# Laadstation.net
KiCad netlist of a schematic drawn in Altium Designer
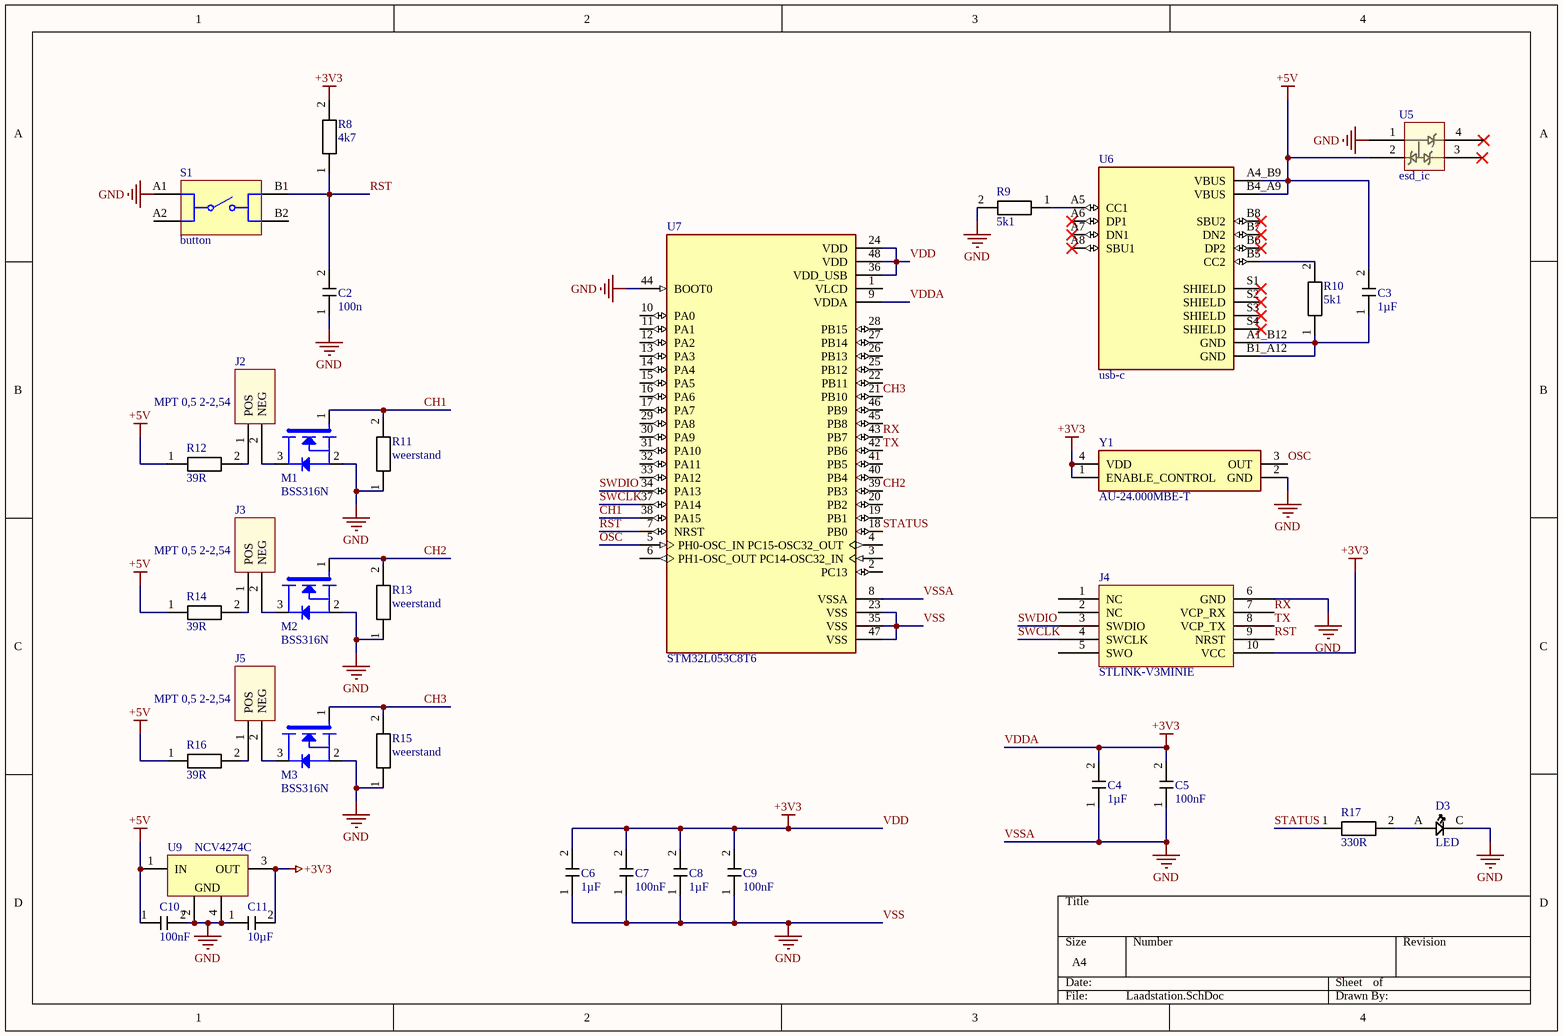
[diagram p0: Laadstation.SchDoc]

(export (version "E")
  (design (tool "Eeschema 10.0.6"))
  (components
    (comp (ref "C2") (value "100n") (footprint "0603") (libsource (lib "condensator") (part "Condensator")))
    (comp (ref "C3") (value "1µF") (footprint "0603") (libsource (lib "condensator") (part "Condensator")))
    (comp (ref "C4") (value "1µF") (footprint "0603") (libsource (lib "Schlib1") (part "cap")))
    (comp (ref "C5") (value "100nF") (footprint "0603") (libsource (lib "Schlib1") (part "cap")))
    (comp (ref "C6") (value "1µF") (footprint "0603") (libsource (lib "condensator") (part "Condensator")))
    (comp (ref "C7") (value "100nF") (footprint "0603") (libsource (lib "condensator") (part "Condensator")))
    (comp (ref "C8") (value "1µF") (footprint "0603") (libsource (lib "condensator") (part "Condensator")))
    (comp (ref "C9") (value "100nF") (footprint "0603") (libsource (lib "condensator") (part "Condensator")))
    (comp (ref "C10") (value "100nF") (footprint "0603") (libsource (lib "Schlib1") (part "cap")))
    (comp (ref "C11") (value "10µF") (footprint "0603") (libsource (lib "Schlib1") (part "cap")))
    (comp (ref "D3") (value "LED") (footprint "LED") (libsource (lib "Schlib1") (part "LED")))
    (comp (ref "J2")
      (value "MPT 0,5 2-2,54")
      (footprint "MPT 0,5 2-2,54")
      (libsource (lib "Schlib1") (part "MPT 0,5 2-2,54"))
    )
    (comp (ref "J3")
      (value "MPT 0,5 2-2,54")
      (footprint "MPT 0,5 2-2,54")
      (libsource (lib "Schlib1") (part "MPT 0,5 2-2,54"))
    )
    (comp (ref "J4")
      (value "STLINK-V3MINIE")
      (footprint "STLINK-V3MINIE")
      (libsource (lib "Schlib1") (part "STLINK-V3MINIE"))
    )
    (comp (ref "J5")
      (value "MPT 0,5 2-2,54")
      (footprint "MPT 0,5 2-2,54")
      (libsource (lib "Schlib1") (part "MPT 0,5 2-2,54"))
    )
    (comp (ref "M1") (value "BSS316N") (footprint "BSS316N") (libsource (lib "Schlib1") (part "BSS316N")))
    (comp (ref "M2") (value "BSS316N") (footprint "BSS316N") (libsource (lib "Schlib1") (part "BSS316N")))
    (comp (ref "M3") (value "BSS316N") (footprint "BSS316N") (libsource (lib "Schlib1") (part "BSS316N")))
    (comp (ref "R8") (value "4k7") (footprint "0603") (libsource (lib "Schlib1") (part "weerstand")))
    (comp (ref "R9") (value "5k1") (footprint "0603") (libsource (lib "Schlib1") (part "weerstand")))
    (comp (ref "R10") (value "5k1") (footprint "0603") (libsource (lib "Schlib1") (part "weerstand")))
    (comp (ref "R11") (value "weerstand") (footprint "0603") (libsource (lib "Schlib1") (part "weerstand")))
    (comp (ref "R12") (value "39R") (footprint "0603") (libsource (lib "Schlib1") (part "weerstand")))
    (comp (ref "R13") (value "weerstand") (footprint "0603") (libsource (lib "Schlib1") (part "weerstand")))
    (comp (ref "R14") (value "39R") (footprint "0603") (libsource (lib "Schlib1") (part "weerstand")))
    (comp (ref "R15") (value "weerstand") (footprint "0603") (libsource (lib "Schlib1") (part "weerstand")))
    (comp (ref "R16") (value "39R") (footprint "0603") (libsource (lib "Schlib1") (part "weerstand")))
    (comp (ref "R17") (value "330R") (footprint "0603") (libsource (lib "Schlib1") (part "weerstand")))
    (comp (ref "S1") (value "button") (footprint "BUTTON") (libsource (lib "Schlib1") (part "button")))
    (comp (ref "U5") (value "esd_ic") (footprint "esd_ic") (libsource (lib "Schlib1") (part "esd_ic")))
    (comp (ref "U6") (value "usb-c") (footprint "usb-c") (libsource (lib "Schlib1") (part "usb-c")))
    (comp (ref "U7")
      (value "STM32L053C8T6")
      (footprint "stm32l053c8t6")
      (libsource (lib "Schlib1") (part "STM32L053C8T6"))
    )
    (comp (ref "U9") (value "NCV4274C") (footprint "NCV4274C") (libsource (lib "Schlib1") (part "NCV4274C")))
    (comp (ref "Y1")
      (value "AU-24.000MBE-T")
      (footprint "AU-24.000MBE-T")
      (libsource (lib "Schlib1") (part "AU-24.000MBE-T"))
    )
  )
  (nets
    (net (code "1") (name "+3V3") (class "Default")
      (node (ref "C11") (pin "2") (pinfunction "G_2") (pintype "passive"))
      (node (ref "C4") (pin "2") (pinfunction "G_2") (pintype "passive"))
      (node (ref "C5") (pin "2") (pinfunction "G_2") (pintype "passive"))
      (node (ref "C6") (pin "2") (pinfunction "G_2") (pintype "passive"))
      (node (ref "C7") (pin "2") (pinfunction "G_2") (pintype "passive"))
      (node (ref "C8") (pin "2") (pinfunction "G_2") (pintype "passive"))
      (node (ref "C9") (pin "2") (pinfunction "G_2") (pintype "passive"))
      (node (ref "J4") (pin "10") (pinfunction "VCC_10") (pintype "passive"))
      (node (ref "R8") (pin "2") (pinfunction "G_2") (pintype "passive"))
      (node (ref "U7") (pin "24") (pinfunction "VDD_24") (pintype "power_in"))
      (node (ref "U7") (pin "36") (pinfunction "VDD_USB_36") (pintype "power_in"))
      (node (ref "U7") (pin "48") (pinfunction "VDD_48") (pintype "power_in"))
      (node (ref "U7") (pin "9") (pinfunction "VDDA_9") (pintype "power_in"))
      (node (ref "U9") (pin "3") (pinfunction "OUT_3") (pintype "power_in"))
      (node (ref "Y1") (pin "1") (pinfunction "ENABLE_CONTROL_1") (pintype "passive"))
      (node (ref "Y1") (pin "4") (pinfunction "VDD_4") (pintype "passive"))
    )
    (net (code "2") (name "+5V") (class "Default")
      (node (ref "C10") (pin "1") (pinfunction "G_1") (pintype "passive"))
      (node (ref "C3") (pin "2") (pinfunction "G_2") (pintype "passive"))
      (node (ref "R12") (pin "1") (pinfunction "1_1") (pintype "passive"))
      (node (ref "R14") (pin "1") (pinfunction "1_1") (pintype "passive"))
      (node (ref "R16") (pin "1") (pinfunction "1_1") (pintype "passive"))
      (node (ref "U5") (pin "2") (pinfunction "2_2") (pintype "passive"))
      (node (ref "U6") (pin "A4_B9") (pinfunction "VBUS_A4_B9") (pintype "power_in"))
      (node (ref "U6") (pin "B4_A9") (pinfunction "VBUS_B4_A9") (pintype "power_in"))
      (node (ref "U9") (pin "1") (pinfunction "IN_1") (pintype "power_in"))
    )
    (net (code "3") (name "/CH1") (class "Default")
      (node (ref "M1") (pin "1") (pinfunction "G_1") (pintype "passive"))
      (node (ref "R11") (pin "2") (pinfunction "G_2") (pintype "passive"))
      (node (ref "U7") (pin "38") (pinfunction "PA15_38") (pintype "bidirectional"))
    )
    (net (code "4") (name "/CH2") (class "Default")
      (node (ref "M2") (pin "1") (pinfunction "G_1") (pintype "passive"))
      (node (ref "R13") (pin "2") (pinfunction "G_2") (pintype "passive"))
      (node (ref "U7") (pin "39") (pinfunction "PB3_39") (pintype "bidirectional"))
    )
    (net (code "5") (name "/CH3") (class "Default")
      (node (ref "M3") (pin "1") (pinfunction "G_1") (pintype "passive"))
      (node (ref "R15") (pin "2") (pinfunction "G_2") (pintype "passive"))
      (node (ref "U7") (pin "21") (pinfunction "PB10_21") (pintype "bidirectional"))
    )
    (net (code "6") (name "/OSC") (class "Default")
      (node (ref "U7") (pin "5") (pinfunction "PH0-OSC_IN_5") (pintype "input"))
      (node (ref "Y1") (pin "3") (pinfunction "OUT_3") (pintype "passive"))
    )
    (net (code "7") (name "/RST") (class "Default")
      (node (ref "C2") (pin "2") (pinfunction "G_2") (pintype "passive"))
      (node (ref "J4") (pin "9") (pinfunction "NRST_9") (pintype "passive"))
      (node (ref "R8") (pin "1") (pinfunction "1_1") (pintype "passive"))
      (node (ref "S1") (pin "B1") (pinfunction "B1_B1") (pintype "passive"))
      (node (ref "U7") (pin "7") (pinfunction "NRST_7") (pintype "bidirectional"))
    )
    (net (code "8") (name "/RX") (class "Default")
      (node (ref "J4") (pin "7") (pinfunction "VCP_RX_7") (pintype "passive"))
      (node (ref "U7") (pin "43") (pinfunction "PB7_43") (pintype "bidirectional"))
    )
    (net (code "9") (name "/STATUS") (class "Default")
      (node (ref "R17") (pin "1") (pinfunction "1_1") (pintype "passive"))
      (node (ref "U7") (pin "18") (pinfunction "PB0_18") (pintype "bidirectional"))
    )
    (net (code "10") (name "/SWCLK") (class "Default")
      (node (ref "J4") (pin "4") (pinfunction "SWCLK_4") (pintype "passive"))
      (node (ref "U7") (pin "37") (pinfunction "PA14_37") (pintype "bidirectional"))
    )
    (net (code "11") (name "/SWDIO") (class "Default")
      (node (ref "J4") (pin "3") (pinfunction "SWDIO_3") (pintype "passive"))
      (node (ref "U7") (pin "34") (pinfunction "PA13_34") (pintype "bidirectional"))
    )
    (net (code "12") (name "/TX") (class "Default")
      (node (ref "J4") (pin "8") (pinfunction "VCP_TX_8") (pintype "passive"))
      (node (ref "U7") (pin "42") (pinfunction "PB6_42") (pintype "bidirectional"))
    )
    (net (code "13") (name "GND") (class "Default")
      (node (ref "C10") (pin "2") (pinfunction "G_2") (pintype "passive"))
      (node (ref "C11") (pin "1") (pinfunction "G_1") (pintype "passive"))
      (node (ref "C2") (pin "1") (pinfunction "G_1") (pintype "passive"))
      (node (ref "C4") (pin "1") (pinfunction "G_1") (pintype "passive"))
      (node (ref "C5") (pin "1") (pinfunction "G_1") (pintype "passive"))
      (node (ref "C6") (pin "1") (pinfunction "G_1") (pintype "passive"))
      (node (ref "C7") (pin "1") (pinfunction "G_1") (pintype "passive"))
      (node (ref "C8") (pin "1") (pinfunction "G_1") (pintype "passive"))
      (node (ref "C9") (pin "1") (pinfunction "G_1") (pintype "passive"))
      (node (ref "D3") (pin "C") (pinfunction "C_C") (pintype "passive"))
      (node (ref "J4") (pin "6") (pinfunction "GND_6") (pintype "passive"))
      (node (ref "M1") (pin "2") (pinfunction "S_2") (pintype "passive"))
      (node (ref "M2") (pin "2") (pinfunction "S_2") (pintype "passive"))
      (node (ref "M3") (pin "2") (pinfunction "S_2") (pintype "passive"))
      (node (ref "R11") (pin "1") (pinfunction "1_1") (pintype "passive"))
      (node (ref "R13") (pin "1") (pinfunction "1_1") (pintype "passive"))
      (node (ref "R15") (pin "1") (pinfunction "1_1") (pintype "passive"))
      (node (ref "R9") (pin "2") (pinfunction "G_2") (pintype "passive"))
      (node (ref "S1") (pin "A1") (pinfunction "A1_A1") (pintype "passive"))
      (node (ref "U5") (pin "1") (pinfunction "1_1") (pintype "passive"))
      (node (ref "U7") (pin "23") (pinfunction "VSS_23") (pintype "power_in"))
      (node (ref "U7") (pin "35") (pinfunction "VSS_35") (pintype "power_in"))
      (node (ref "U7") (pin "44") (pinfunction "BOOT0_44") (pintype "input"))
      (node (ref "U7") (pin "47") (pinfunction "VSS_47") (pintype "power_in"))
      (node (ref "U7") (pin "8") (pinfunction "VSSA_8") (pintype "power_in"))
      (node (ref "U9") (pin "2") (pinfunction "GND_2") (pintype "power_in"))
      (node (ref "U9") (pin "4") (pinfunction "GND_4") (pintype "power_in"))
      (node (ref "Y1") (pin "2") (pinfunction "GND_2") (pintype "passive"))
    )
    (net (code "14") (name "Net-(C3-G-Pad1)") (class "Default")
      (node (ref "C3") (pin "1") (pinfunction "G_1") (pintype "passive"))
      (node (ref "R10") (pin "1") (pinfunction "1_1") (pintype "passive"))
      (node (ref "U6") (pin "A1_B12") (pinfunction "GND_A1_B12") (pintype "power_in"))
      (node (ref "U6") (pin "B1_A12") (pinfunction "GND_B1_A12") (pintype "power_in"))
    )
    (net (code "15") (name "Net-(J2-NEG)") (class "Default")
      (node (ref "J2") (pin "2") (pinfunction "NEG_2") (pintype "passive"))
      (node (ref "M1") (pin "3") (pinfunction "D_3") (pintype "passive"))
    )
    (net (code "16") (name "Net-(J2-POS)") (class "Default")
      (node (ref "J2") (pin "1") (pinfunction "POS_1") (pintype "passive"))
      (node (ref "R12") (pin "2") (pinfunction "G_2") (pintype "passive"))
    )
    (net (code "17") (name "Net-(J3-NEG)") (class "Default")
      (node (ref "J3") (pin "2") (pinfunction "NEG_2") (pintype "passive"))
      (node (ref "M2") (pin "3") (pinfunction "D_3") (pintype "passive"))
    )
    (net (code "18") (name "Net-(J3-POS)") (class "Default")
      (node (ref "J3") (pin "1") (pinfunction "POS_1") (pintype "passive"))
      (node (ref "R14") (pin "2") (pinfunction "G_2") (pintype "passive"))
    )
    (net (code "19") (name "Net-(J5-NEG)") (class "Default")
      (node (ref "J5") (pin "2") (pinfunction "NEG_2") (pintype "passive"))
      (node (ref "M3") (pin "3") (pinfunction "D_3") (pintype "passive"))
    )
    (net (code "20") (name "Net-(J5-POS)") (class "Default")
      (node (ref "J5") (pin "1") (pinfunction "POS_1") (pintype "passive"))
      (node (ref "R16") (pin "2") (pinfunction "G_2") (pintype "passive"))
    )
    (net (code "21") (name "Net-(R10-G)") (class "Default")
      (node (ref "R10") (pin "2") (pinfunction "G_2") (pintype "passive"))
      (node (ref "U6") (pin "B5") (pinfunction "CC2_B5") (pintype "bidirectional"))
    )
    (net (code "22") (name "Net-(R17-G)") (class "Default")
      (node (ref "D3") (pin "A") (pinfunction "A_A") (pintype "passive"))
      (node (ref "R17") (pin "2") (pinfunction "G_2") (pintype "passive"))
    )
    (net (code "23") (name "Net-(U6-CC1)") (class "Default")
      (node (ref "R9") (pin "1") (pinfunction "1_1") (pintype "passive"))
      (node (ref "U6") (pin "A5") (pinfunction "CC1_A5") (pintype "bidirectional"))
    )
    (net (code "24") (name "unconnected-(J4-NC-Pad1)") (class "Default")
      (node (ref "J4") (pin "1") (pinfunction "NC_1") (pintype "passive"))
    )
    (net (code "25") (name "unconnected-(J4-NC-Pad2)") (class "Default")
      (node (ref "J4") (pin "2") (pinfunction "NC_2") (pintype "passive"))
    )
    (net (code "26") (name "unconnected-(J4-SWO-Pad5)") (class "Default")
      (node (ref "J4") (pin "5") (pinfunction "SWO_5") (pintype "passive"))
    )
    (net (code "27") (name "unconnected-(S1-PadA2)") (class "Default")
      (node (ref "S1") (pin "A2") (pinfunction "A2_A2") (pintype "passive"))
    )
    (net (code "28") (name "unconnected-(S1-PadB2)") (class "Default")
      (node (ref "S1") (pin "B2") (pinfunction "B2_B2") (pintype "passive"))
    )
    (net (code "29") (name "unconnected-(U5-Pad3)") (class "Default")
      (node (ref "U5") (pin "3") (pinfunction "3_3") (pintype "passive+no_connect"))
    )
    (net (code "30") (name "unconnected-(U5-Pad4)") (class "Default")
      (node (ref "U5") (pin "4") (pinfunction "4_4") (pintype "passive+no_connect"))
    )
    (net (code "31") (name "unconnected-(U6-DN1-PadA7)") (class "Default")
      (node (ref "U6") (pin "A7") (pinfunction "DN1_A7") (pintype "bidirectional+no_connect"))
    )
    (net (code "32") (name "unconnected-(U6-DN2-PadB7)") (class "Default")
      (node (ref "U6") (pin "B7") (pinfunction "DN2_B7") (pintype "bidirectional+no_connect"))
    )
    (net (code "33") (name "unconnected-(U6-DP1-PadA6)") (class "Default")
      (node (ref "U6") (pin "A6") (pinfunction "DP1_A6") (pintype "bidirectional+no_connect"))
    )
    (net (code "34") (name "unconnected-(U6-DP2-PadB6)") (class "Default")
      (node (ref "U6") (pin "B6") (pinfunction "DP2_B6") (pintype "bidirectional+no_connect"))
    )
    (net (code "35") (name "unconnected-(U6-SBU1-PadA8)") (class "Default")
      (node (ref "U6") (pin "A8") (pinfunction "SBU1_A8") (pintype "bidirectional+no_connect"))
    )
    (net (code "36") (name "unconnected-(U6-SBU2-PadB8)") (class "Default")
      (node (ref "U6") (pin "B8") (pinfunction "SBU2_B8") (pintype "bidirectional+no_connect"))
    )
    (net (code "37") (name "unconnected-(U6-SHIELD-PadS1)") (class "Default")
      (node (ref "U6") (pin "S1") (pinfunction "SHIELD_S1") (pintype "passive+no_connect"))
    )
    (net (code "38") (name "unconnected-(U6-SHIELD-PadS2)") (class "Default")
      (node (ref "U6") (pin "S2") (pinfunction "SHIELD_S2") (pintype "passive+no_connect"))
    )
    (net (code "39") (name "unconnected-(U6-SHIELD-PadS3)") (class "Default")
      (node (ref "U6") (pin "S3") (pinfunction "SHIELD_S3") (pintype "passive+no_connect"))
    )
    (net (code "40") (name "unconnected-(U6-SHIELD-PadS4)") (class "Default")
      (node (ref "U6") (pin "S4") (pinfunction "SHIELD_S4") (pintype "passive+no_connect"))
    )
    (net (code "41") (name "unconnected-(U7-PA0-Pad10)") (class "Default")
      (node (ref "U7") (pin "10") (pinfunction "PA0_10") (pintype "bidirectional"))
    )
    (net (code "42") (name "unconnected-(U7-PA1-Pad11)") (class "Default")
      (node (ref "U7") (pin "11") (pinfunction "PA1_11") (pintype "bidirectional"))
    )
    (net (code "43") (name "unconnected-(U7-PA2-Pad12)") (class "Default")
      (node (ref "U7") (pin "12") (pinfunction "PA2_12") (pintype "bidirectional"))
    )
    (net (code "44") (name "unconnected-(U7-PA3-Pad13)") (class "Default")
      (node (ref "U7") (pin "13") (pinfunction "PA3_13") (pintype "bidirectional"))
    )
    (net (code "45") (name "unconnected-(U7-PA4-Pad14)") (class "Default")
      (node (ref "U7") (pin "14") (pinfunction "PA4_14") (pintype "bidirectional"))
    )
    (net (code "46") (name "unconnected-(U7-PA5-Pad15)") (class "Default")
      (node (ref "U7") (pin "15") (pinfunction "PA5_15") (pintype "bidirectional"))
    )
    (net (code "47") (name "unconnected-(U7-PA6-Pad16)") (class "Default")
      (node (ref "U7") (pin "16") (pinfunction "PA6_16") (pintype "bidirectional"))
    )
    (net (code "48") (name "unconnected-(U7-PA7-Pad17)") (class "Default")
      (node (ref "U7") (pin "17") (pinfunction "PA7_17") (pintype "bidirectional"))
    )
    (net (code "49") (name "unconnected-(U7-PA8-Pad29)") (class "Default")
      (node (ref "U7") (pin "29") (pinfunction "PA8_29") (pintype "bidirectional"))
    )
    (net (code "50") (name "unconnected-(U7-PA9-Pad30)") (class "Default")
      (node (ref "U7") (pin "30") (pinfunction "PA9_30") (pintype "bidirectional"))
    )
    (net (code "51") (name "unconnected-(U7-PA10-Pad31)") (class "Default")
      (node (ref "U7") (pin "31") (pinfunction "PA10_31") (pintype "bidirectional"))
    )
    (net (code "52") (name "unconnected-(U7-PA11-Pad32)") (class "Default")
      (node (ref "U7") (pin "32") (pinfunction "PA11_32") (pintype "bidirectional"))
    )
    (net (code "53") (name "unconnected-(U7-PA12-Pad33)") (class "Default")
      (node (ref "U7") (pin "33") (pinfunction "PA12_33") (pintype "bidirectional"))
    )
    (net (code "54") (name "unconnected-(U7-PB1-Pad19)") (class "Default")
      (node (ref "U7") (pin "19") (pinfunction "PB1_19") (pintype "bidirectional"))
    )
    (net (code "55") (name "unconnected-(U7-PB2-Pad20)") (class "Default")
      (node (ref "U7") (pin "20") (pinfunction "PB2_20") (pintype "bidirectional"))
    )
    (net (code "56") (name "unconnected-(U7-PB4-Pad40)") (class "Default")
      (node (ref "U7") (pin "40") (pinfunction "PB4_40") (pintype "bidirectional"))
    )
    (net (code "57") (name "unconnected-(U7-PB5-Pad41)") (class "Default")
      (node (ref "U7") (pin "41") (pinfunction "PB5_41") (pintype "bidirectional"))
    )
    (net (code "58") (name "unconnected-(U7-PB8-Pad45)") (class "Default")
      (node (ref "U7") (pin "45") (pinfunction "PB8_45") (pintype "bidirectional"))
    )
    (net (code "59") (name "unconnected-(U7-PB9-Pad46)") (class "Default")
      (node (ref "U7") (pin "46") (pinfunction "PB9_46") (pintype "bidirectional"))
    )
    (net (code "60") (name "unconnected-(U7-PB11-Pad22)") (class "Default")
      (node (ref "U7") (pin "22") (pinfunction "PB11_22") (pintype "bidirectional"))
    )
    (net (code "61") (name "unconnected-(U7-PB12-Pad25)") (class "Default")
      (node (ref "U7") (pin "25") (pinfunction "PB12_25") (pintype "bidirectional"))
    )
    (net (code "62") (name "unconnected-(U7-PB13-Pad26)") (class "Default")
      (node (ref "U7") (pin "26") (pinfunction "PB13_26") (pintype "bidirectional"))
    )
    (net (code "63") (name "unconnected-(U7-PB14-Pad27)") (class "Default")
      (node (ref "U7") (pin "27") (pinfunction "PB14_27") (pintype "bidirectional"))
    )
    (net (code "64") (name "unconnected-(U7-PB15-Pad28)") (class "Default")
      (node (ref "U7") (pin "28") (pinfunction "PB15_28") (pintype "bidirectional"))
    )
    (net (code "65") (name "unconnected-(U7-PC13-Pad2)") (class "Default")
      (node (ref "U7") (pin "2") (pinfunction "PC13_2") (pintype "bidirectional"))
    )
    (net (code "66") (name "unconnected-(U7-PC14-OSC32_IN-Pad3)") (class "Default")
      (node (ref "U7") (pin "3") (pinfunction "PC14-OSC32_IN_3") (pintype "input"))
    )
    (net (code "67") (name "unconnected-(U7-PC15-OSC32_OUT-Pad4)") (class "Default")
      (node (ref "U7") (pin "4") (pinfunction "PC15-OSC32_OUT_4") (pintype "output"))
    )
    (net (code "68") (name "unconnected-(U7-PH1-OSC_OUT-Pad6)") (class "Default")
      (node (ref "U7") (pin "6") (pinfunction "PH1-OSC_OUT_6") (pintype "output"))
    )
    (net (code "69") (name "unconnected-(U7-VLCD-Pad1)") (class "Default")
      (node (ref "U7") (pin "1") (pinfunction "VLCD_1") (pintype "power_in"))
    )
  )
)
